# micron_P3.net
KiCad netlist of a schematic drawn in Altium Designer
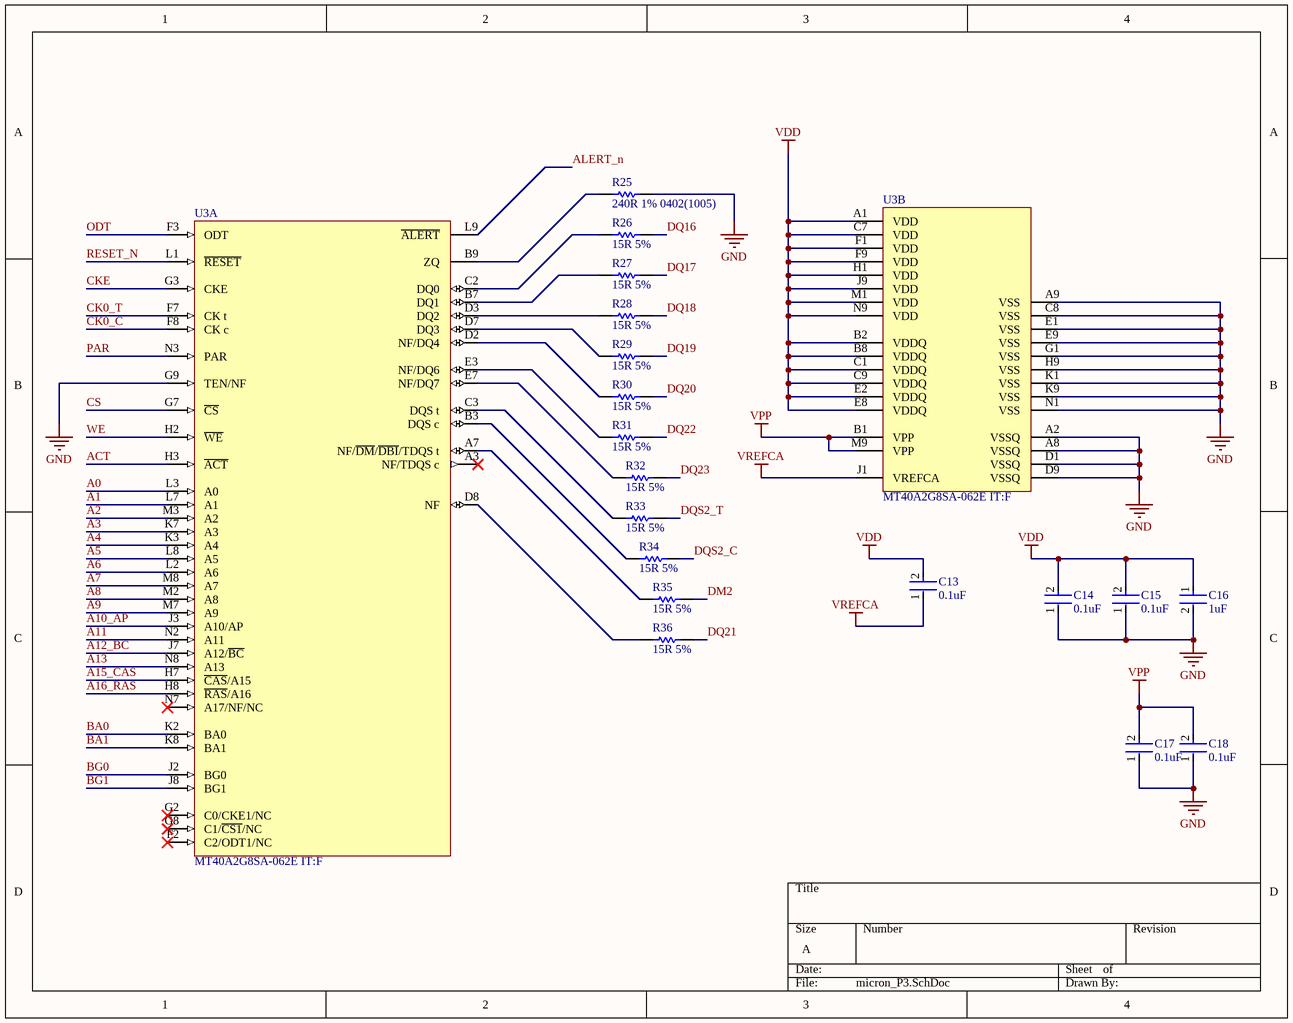
[diagram p0: micron_P3.SchDoc]

(export (version "E")
  (design (tool "Eeschema 10.0.6"))
  (components
    (comp (ref "C13")
      (value "0.1uF")
      (footprint "FP-GRM15-MFG")
      (description "CAP CER 0.1UF 16V X7R 0402")
      (fields (field (name "MANUFACTURER PART NUMBER") "GRM155R71C104KA88D") (field (name "TOLERANCE") "10%"))
      (libsource (lib "Altium Content Vault") (part "236180d848d6139a670b325ea6854c9"))
    )
    (comp (ref "C14")
      (value "0.1uF")
      (footprint "FP-GRM15-MFG")
      (description "CAP CER 0.1UF 16V X7R 0402")
      (fields (field (name "MANUFACTURER PART NUMBER") "GRM155R71C104KA88D") (field (name "TOLERANCE") "10%"))
      (libsource (lib "Altium Content Vault") (part "236180d848d6139a670b325ea6854c9"))
    )
    (comp (ref "C15")
      (value "0.1uF")
      (footprint "FP-GRM15-MFG")
      (description "CAP CER 0.1UF 16V X7R 0402")
      (fields (field (name "MANUFACTURER PART NUMBER") "GRM155R71C104KA88D") (field (name "TOLERANCE") "10%"))
      (libsource (lib "Altium Content Vault") (part "236180d848d6139a670b325ea6854c9"))
    )
    (comp (ref "C16")
      (value "1uF")
      (footprint "FP-CL511-IPC_C")
      (description "Cap Ceramic 1uF 10V X5R ±10% SMD 0402 +85°C Paper T/R")
      (fields (field (name "TOLERANCE") "10%"))
      (libsource (lib "Altium Content Vault") (part "b4654b650e69147ec39a6b967a45e02"))
    )
    (comp (ref "C17")
      (value "0.1uF")
      (footprint "FP-GRM15-MFG")
      (description "CAP CER 0.1UF 16V X7R 0402")
      (fields (field (name "MANUFACTURER PART NUMBER") "GRM155R71C104KA88D") (field (name "TOLERANCE") "10%"))
      (libsource (lib "Altium Content Vault") (part "236180d848d6139a670b325ea6854c9"))
    )
    (comp (ref "C18")
      (value "0.1uF")
      (footprint "FP-GRM15-MFG")
      (description "CAP CER 0.1UF 16V X7R 0402")
      (fields (field (name "MANUFACTURER PART NUMBER") "GRM155R71C104KA88D") (field (name "TOLERANCE") "10%"))
      (libsource (lib "Altium Content Vault") (part "236180d848d6139a670b325ea6854c9"))
    )
    (comp (ref "R25")
      (value "240R 1% 0402(1005)")
      (footprint "RESC0402(1005)_L")
      (description "240R 0.063W 1% 0402 (1005 Metric)  SMD")
      (fields (field (name "POWER") "0.063 W") (field (name "TOLERANCE") "1 %"))
      (libsource (lib "Altium Content Vault") (part "RES"))
    )
    (comp (ref "R26")
      (value "15R 5%")
      (footprint "RESC1005X40X25LL05T10")
      (fields (field (name "MANUFACTURER") "Yageo / Phycomp") (field (name "PART NUMBER") "RC0402FR-0715RL"))
      (libsource (lib "Altium Content Vault") (part "RES"))
    )
    (comp (ref "R27")
      (value "15R 5%")
      (footprint "RESC1005X40X25LL05T10")
      (fields (field (name "MANUFACTURER") "Yageo / Phycomp") (field (name "PART NUMBER") "RC0402FR-0715RL"))
      (libsource (lib "Altium Content Vault") (part "RES"))
    )
    (comp (ref "R28")
      (value "15R 5%")
      (footprint "RESC1005X40X25LL05T10")
      (fields (field (name "MANUFACTURER") "Yageo / Phycomp") (field (name "PART NUMBER") "RC0402FR-0715RL"))
      (libsource (lib "Altium Content Vault") (part "RES"))
    )
    (comp (ref "R29")
      (value "15R 5%")
      (footprint "RESC1005X40X25LL05T10")
      (fields (field (name "MANUFACTURER") "Yageo / Phycomp") (field (name "PART NUMBER") "RC0402FR-0715RL"))
      (libsource (lib "Altium Content Vault") (part "RES"))
    )
    (comp (ref "R30")
      (value "15R 5%")
      (footprint "RESC1005X40X25LL05T10")
      (fields (field (name "MANUFACTURER") "Yageo / Phycomp") (field (name "PART NUMBER") "RC0402FR-0715RL"))
      (libsource (lib "Altium Content Vault") (part "RES"))
    )
    (comp (ref "R31")
      (value "15R 5%")
      (footprint "RESC1005X40X25LL05T10")
      (fields (field (name "MANUFACTURER") "Yageo / Phycomp") (field (name "PART NUMBER") "RC0402FR-0715RL"))
      (libsource (lib "Altium Content Vault") (part "RES"))
    )
    (comp (ref "R32")
      (value "15R 5%")
      (footprint "RESC1005X40X25LL05T10")
      (fields (field (name "MANUFACTURER") "Yageo / Phycomp") (field (name "PART NUMBER") "RC0402FR-0715RL"))
      (libsource (lib "Altium Content Vault") (part "RES"))
    )
    (comp (ref "R33")
      (value "15R 5%")
      (footprint "RESC1005X40X25LL05T10")
      (fields (field (name "MANUFACTURER") "Yageo / Phycomp") (field (name "PART NUMBER") "RC0402FR-0715RL"))
      (libsource (lib "Altium Content Vault") (part "RES"))
    )
    (comp (ref "R34")
      (value "15R 5%")
      (footprint "RESC1005X40X25LL05T10")
      (fields (field (name "MANUFACTURER") "Yageo / Phycomp") (field (name "PART NUMBER") "RC0402FR-0715RL"))
      (libsource (lib "Altium Content Vault") (part "RES"))
    )
    (comp (ref "R35")
      (value "15R 5%")
      (footprint "RESC1005X40X25LL05T10")
      (fields (field (name "MANUFACTURER") "Yageo / Phycomp") (field (name "PART NUMBER") "RC0402FR-0715RL"))
      (libsource (lib "Altium Content Vault") (part "RES"))
    )
    (comp (ref "R36")
      (value "15R 5%")
      (footprint "RESC1005X40X25LL05T10")
      (fields (field (name "MANUFACTURER") "Yageo / Phycomp") (field (name "PART NUMBER") "RC0402FR-0715RL"))
      (libsource (lib "Altium Content Vault") (part "RES"))
    )
    (comp (ref "U3")
      (value "MT40A2G8SA-062E IT:F")
      (footprint "SA_MFG")
      (description "DRAMChip DDR4 SDRAM 16Gbit 2Gx8 1.2V 78-Pin FBGA Tray")
      (libsource (lib "Altium Content Vault") (part "d28cb998757b614ee3280f10a38a3b1"))
    )
  )
  (nets
    (net (code "1") (name "/A0") (class "Default")
      (node (ref "U3") (pin "L3") (pinfunction "A0_L3") (pintype "input"))
    )
    (net (code "2") (name "/A1") (class "Default")
      (node (ref "U3") (pin "L7") (pinfunction "A1_L7") (pintype "input"))
    )
    (net (code "3") (name "/A2") (class "Default")
      (node (ref "U3") (pin "M3") (pinfunction "A2_M3") (pintype "input"))
    )
    (net (code "4") (name "/A3") (class "Default")
      (node (ref "U3") (pin "K7") (pinfunction "A3_K7") (pintype "input"))
    )
    (net (code "5") (name "/A4") (class "Default")
      (node (ref "U3") (pin "K3") (pinfunction "A4_K3") (pintype "input"))
    )
    (net (code "6") (name "/A5") (class "Default")
      (node (ref "U3") (pin "L8") (pinfunction "A5_L8") (pintype "input"))
    )
    (net (code "7") (name "/A6") (class "Default")
      (node (ref "U3") (pin "L2") (pinfunction "A6_L2") (pintype "input"))
    )
    (net (code "8") (name "/A7") (class "Default")
      (node (ref "U3") (pin "M8") (pinfunction "A7_M8") (pintype "input"))
    )
    (net (code "9") (name "/A8") (class "Default")
      (node (ref "U3") (pin "M2") (pinfunction "A8_M2") (pintype "input"))
    )
    (net (code "10") (name "/A9") (class "Default")
      (node (ref "U3") (pin "M7") (pinfunction "A9_M7") (pintype "input"))
    )
    (net (code "11") (name "/A10_AP") (class "Default")
      (node (ref "U3") (pin "J3") (pinfunction "A10/AP_J3") (pintype "input"))
    )
    (net (code "12") (name "/A11") (class "Default")
      (node (ref "U3") (pin "N2") (pinfunction "A11_N2") (pintype "input"))
    )
    (net (code "13") (name "/A12_BC") (class "Default")
      (node (ref "U3") (pin "J7") (pinfunction "A12/~{BC}_J7") (pintype "input"))
    )
    (net (code "14") (name "/A13") (class "Default")
      (node (ref "U3") (pin "N8") (pinfunction "A13_N8") (pintype "input"))
    )
    (net (code "15") (name "/A15_CAS") (class "Default")
      (node (ref "U3") (pin "H7") (pinfunction "~{CAS}/A15_H7") (pintype "input"))
    )
    (net (code "16") (name "/A16_RAS") (class "Default")
      (node (ref "U3") (pin "H8") (pinfunction "~{RAS}/A16_H8") (pintype "input"))
    )
    (net (code "17") (name "/ACT") (class "Default")
      (node (ref "U3") (pin "H3") (pinfunction "~{ACT}_H3") (pintype "input"))
    )
    (net (code "18") (name "/ALERT_n") (class "Default")
      (node (ref "U3") (pin "L9") (pinfunction "~{ALERT}_L9") (pintype "open_collector"))
    )
    (net (code "19") (name "/BA0") (class "Default")
      (node (ref "U3") (pin "K2") (pinfunction "BA0_K2") (pintype "input"))
    )
    (net (code "20") (name "/BA1") (class "Default")
      (node (ref "U3") (pin "K8") (pinfunction "BA1_K8") (pintype "input"))
    )
    (net (code "21") (name "/BG0") (class "Default")
      (node (ref "U3") (pin "J2") (pinfunction "BG0_J2") (pintype "input"))
    )
    (net (code "22") (name "/BG1") (class "Default")
      (node (ref "U3") (pin "J8") (pinfunction "BG1_J8") (pintype "input"))
    )
    (net (code "23") (name "/CK0_C") (class "Default")
      (node (ref "U3") (pin "F8") (pinfunction "CK_c_F8") (pintype "input"))
    )
    (net (code "24") (name "/CK0_T") (class "Default")
      (node (ref "U3") (pin "F7") (pinfunction "CK_t_F7") (pintype "input"))
    )
    (net (code "25") (name "/CKE") (class "Default")
      (node (ref "U3") (pin "G3") (pinfunction "CKE_G3") (pintype "input"))
    )
    (net (code "26") (name "/CS") (class "Default")
      (node (ref "U3") (pin "G7") (pinfunction "~{CS}_G7") (pintype "input"))
    )
    (net (code "27") (name "/DM2") (class "Default")
      (node (ref "R35") (pin "2") (pinfunction "2_2") (pintype "passive"))
    )
    (net (code "28") (name "/DQ16") (class "Default")
      (node (ref "R26") (pin "2") (pinfunction "2_2") (pintype "passive"))
    )
    (net (code "29") (name "/DQ17") (class "Default")
      (node (ref "R27") (pin "2") (pinfunction "2_2") (pintype "passive"))
    )
    (net (code "30") (name "/DQ18") (class "Default")
      (node (ref "R28") (pin "2") (pinfunction "2_2") (pintype "passive"))
    )
    (net (code "31") (name "/DQ19") (class "Default")
      (node (ref "R29") (pin "2") (pinfunction "2_2") (pintype "passive"))
    )
    (net (code "32") (name "/DQ20") (class "Default")
      (node (ref "R30") (pin "2") (pinfunction "2_2") (pintype "passive"))
    )
    (net (code "33") (name "/DQ21") (class "Default")
      (node (ref "R36") (pin "2") (pinfunction "2_2") (pintype "passive"))
    )
    (net (code "34") (name "/DQ22") (class "Default")
      (node (ref "R31") (pin "2") (pinfunction "2_2") (pintype "passive"))
    )
    (net (code "35") (name "/DQ23") (class "Default")
      (node (ref "R32") (pin "2") (pinfunction "2_2") (pintype "passive"))
    )
    (net (code "36") (name "/DQS2_C") (class "Default")
      (node (ref "R34") (pin "2") (pinfunction "2_2") (pintype "passive"))
    )
    (net (code "37") (name "/DQS2_T") (class "Default")
      (node (ref "R33") (pin "2") (pinfunction "2_2") (pintype "passive"))
    )
    (net (code "38") (name "/ODT") (class "Default")
      (node (ref "U3") (pin "F3") (pinfunction "ODT_F3") (pintype "input"))
    )
    (net (code "39") (name "/PAR") (class "Default")
      (node (ref "U3") (pin "N3") (pinfunction "PAR_N3") (pintype "input"))
    )
    (net (code "40") (name "/RESET_N") (class "Default")
      (node (ref "U3") (pin "L1") (pinfunction "~{RESET}_L1") (pintype "input"))
    )
    (net (code "41") (name "/WE") (class "Default")
      (node (ref "U3") (pin "H2") (pinfunction "~{WE}_H2") (pintype "input"))
    )
    (net (code "42") (name "GND") (class "Default")
      (node (ref "C14") (pin "1") (pinfunction "1_1") (pintype "passive"))
      (node (ref "C15") (pin "1") (pinfunction "1_1") (pintype "passive"))
      (node (ref "C16") (pin "2") (pinfunction "2_2") (pintype "passive"))
      (node (ref "C17") (pin "1") (pinfunction "1_1") (pintype "passive"))
      (node (ref "C18") (pin "1") (pinfunction "1_1") (pintype "passive"))
      (node (ref "R25") (pin "2") (pinfunction "2_2") (pintype "passive"))
      (node (ref "U3") (pin "A2") (pinfunction "VSSQ_A2") (pintype "power_in"))
      (node (ref "U3") (pin "A8") (pinfunction "VSSQ_A8") (pintype "power_in"))
      (node (ref "U3") (pin "A9") (pinfunction "VSS_A9") (pintype "power_in"))
      (node (ref "U3") (pin "C8") (pinfunction "VSS_C8") (pintype "power_in"))
      (node (ref "U3") (pin "D1") (pinfunction "VSSQ_D1") (pintype "power_in"))
      (node (ref "U3") (pin "D9") (pinfunction "VSSQ_D9") (pintype "power_in"))
      (node (ref "U3") (pin "E1") (pinfunction "VSS_E1") (pintype "power_in"))
      (node (ref "U3") (pin "E9") (pinfunction "VSS_E9") (pintype "power_in"))
      (node (ref "U3") (pin "G1") (pinfunction "VSS_G1") (pintype "power_in"))
      (node (ref "U3") (pin "G9") (pinfunction "TEN/NF_G9") (pintype "input"))
      (node (ref "U3") (pin "H9") (pinfunction "VSS_H9") (pintype "power_in"))
      (node (ref "U3") (pin "K1") (pinfunction "VSS_K1") (pintype "power_in"))
      (node (ref "U3") (pin "K9") (pinfunction "VSS_K9") (pintype "power_in"))
      (node (ref "U3") (pin "N1") (pinfunction "VSS_N1") (pintype "power_in"))
    )
    (net (code "43") (name "Net-(U3A-DQ0)") (class "Default")
      (node (ref "R26") (pin "1") (pinfunction "1_1") (pintype "passive"))
      (node (ref "U3") (pin "C2") (pinfunction "DQ0_C2") (pintype "bidirectional"))
    )
    (net (code "44") (name "Net-(U3A-DQ1)") (class "Default")
      (node (ref "R27") (pin "1") (pinfunction "1_1") (pintype "passive"))
      (node (ref "U3") (pin "B7") (pinfunction "DQ1_B7") (pintype "bidirectional"))
    )
    (net (code "45") (name "Net-(U3A-DQ2)") (class "Default")
      (node (ref "R28") (pin "1") (pinfunction "1_1") (pintype "passive"))
      (node (ref "U3") (pin "D3") (pinfunction "DQ2_D3") (pintype "bidirectional"))
    )
    (net (code "46") (name "Net-(U3A-DQ3)") (class "Default")
      (node (ref "R29") (pin "1") (pinfunction "1_1") (pintype "passive"))
      (node (ref "U3") (pin "D7") (pinfunction "DQ3_D7") (pintype "bidirectional"))
    )
    (net (code "47") (name "Net-(U3A-DQS_c)") (class "Default")
      (node (ref "R34") (pin "1") (pinfunction "1_1") (pintype "passive"))
      (node (ref "U3") (pin "B3") (pinfunction "DQS_c_B3") (pintype "bidirectional"))
    )
    (net (code "48") (name "Net-(U3A-DQS_t)") (class "Default")
      (node (ref "R33") (pin "1") (pinfunction "1_1") (pintype "passive"))
      (node (ref "U3") (pin "C3") (pinfunction "DQS_t_C3") (pintype "bidirectional"))
    )
    (net (code "49") (name "Net-(U3A-NF)") (class "Default")
      (node (ref "R36") (pin "1") (pinfunction "1_1") (pintype "passive"))
      (node (ref "U3") (pin "D8") (pinfunction "NF_D8") (pintype "bidirectional"))
    )
    (net (code "50") (name "Net-(U3A-NF{slash}DQ4)") (class "Default")
      (node (ref "R30") (pin "1") (pinfunction "1_1") (pintype "passive"))
      (node (ref "U3") (pin "D2") (pinfunction "NF/DQ4_D2") (pintype "bidirectional"))
    )
    (net (code "51") (name "Net-(U3A-NF{slash}DQ6)") (class "Default")
      (node (ref "R31") (pin "1") (pinfunction "1_1") (pintype "passive"))
      (node (ref "U3") (pin "E3") (pinfunction "NF/DQ6_E3") (pintype "bidirectional"))
    )
    (net (code "52") (name "Net-(U3A-NF{slash}DQ7)") (class "Default")
      (node (ref "R32") (pin "1") (pinfunction "1_1") (pintype "passive"))
      (node (ref "U3") (pin "E7") (pinfunction "NF/DQ7_E7") (pintype "bidirectional"))
    )
    (net (code "53") (name "Net-(U3A-NF{slash}~{DM}{slash}~{DBI}{slash}TDQS_t)") (class "Default")
      (node (ref "R35") (pin "1") (pinfunction "1_1") (pintype "passive"))
      (node (ref "U3") (pin "A7") (pinfunction "NF/~{DM}/~{DBI}/TDQS_t_A7") (pintype "bidirectional"))
    )
    (net (code "54") (name "Net-(U3A-ZQ)") (class "Default")
      (node (ref "R25") (pin "1") (pinfunction "1_1") (pintype "passive"))
      (node (ref "U3") (pin "B9") (pinfunction "ZQ_B9") (pintype "passive"))
    )
    (net (code "55") (name "VDD") (class "Default")
      (node (ref "C13") (pin "2") (pinfunction "2_2") (pintype "passive"))
      (node (ref "C14") (pin "2") (pinfunction "2_2") (pintype "passive"))
      (node (ref "C15") (pin "2") (pinfunction "2_2") (pintype "passive"))
      (node (ref "C16") (pin "1") (pinfunction "1_1") (pintype "passive"))
      (node (ref "U3") (pin "A1") (pinfunction "VDD_A1") (pintype "power_in"))
      (node (ref "U3") (pin "B2") (pinfunction "VDDQ_B2") (pintype "power_in"))
      (node (ref "U3") (pin "B8") (pinfunction "VDDQ_B8") (pintype "power_in"))
      (node (ref "U3") (pin "C1") (pinfunction "VDDQ_C1") (pintype "power_in"))
      (node (ref "U3") (pin "C7") (pinfunction "VDD_C7") (pintype "power_in"))
      (node (ref "U3") (pin "C9") (pinfunction "VDDQ_C9") (pintype "power_in"))
      (node (ref "U3") (pin "E2") (pinfunction "VDDQ_E2") (pintype "power_in"))
      (node (ref "U3") (pin "E8") (pinfunction "VDDQ_E8") (pintype "power_in"))
      (node (ref "U3") (pin "F1") (pinfunction "VDD_F1") (pintype "power_in"))
      (node (ref "U3") (pin "F9") (pinfunction "VDD_F9") (pintype "power_in"))
      (node (ref "U3") (pin "H1") (pinfunction "VDD_H1") (pintype "power_in"))
      (node (ref "U3") (pin "J9") (pinfunction "VDD_J9") (pintype "power_in"))
      (node (ref "U3") (pin "M1") (pinfunction "VDD_M1") (pintype "power_in"))
      (node (ref "U3") (pin "N9") (pinfunction "VDD_N9") (pintype "power_in"))
    )
    (net (code "56") (name "VPP") (class "Default")
      (node (ref "C17") (pin "2") (pinfunction "2_2") (pintype "passive"))
      (node (ref "C18") (pin "2") (pinfunction "2_2") (pintype "passive"))
      (node (ref "U3") (pin "B1") (pinfunction "VPP_B1") (pintype "power_in"))
      (node (ref "U3") (pin "M9") (pinfunction "VPP_M9") (pintype "power_in"))
    )
    (net (code "57") (name "VREFCA") (class "Default")
      (node (ref "C13") (pin "1") (pinfunction "1_1") (pintype "passive"))
      (node (ref "U3") (pin "J1") (pinfunction "VREFCA_J1") (pintype "power_in"))
    )
    (net (code "58") (name "unconnected-(U3A-A17{slash}NF{slash}NC-PadN7)") (class "Default")
      (node (ref "U3") (pin "N7") (pinfunction "A17/NF/NC_N7") (pintype "input+no_connect"))
    )
    (net (code "59") (name "unconnected-(U3A-C0{slash}CKE1{slash}NC-PadG2)") (class "Default")
      (node (ref "U3") (pin "G2") (pinfunction "C0/CKE1/NC_G2") (pintype "input+no_connect"))
    )
    (net (code "60") (name "unconnected-(U3A-C1{slash}~{CS1}{slash}NC-PadG8)") (class "Default")
      (node (ref "U3") (pin "G8") (pinfunction "C1/~{CS1}/NC_G8") (pintype "input+no_connect"))
    )
    (net (code "61") (name "unconnected-(U3A-C2{slash}ODT1{slash}NC-PadF2)") (class "Default")
      (node (ref "U3") (pin "F2") (pinfunction "C2/ODT1/NC_F2") (pintype "input+no_connect"))
    )
    (net (code "62") (name "unconnected-(U3A-NF{slash}TDQS_c-PadA3)") (class "Default")
      (node (ref "U3") (pin "A3") (pinfunction "NF/TDQS_c_A3") (pintype "output+no_connect"))
    )
  )
)
